# Main.net
KiCad netlist of a schematic drawn in Altium Designer
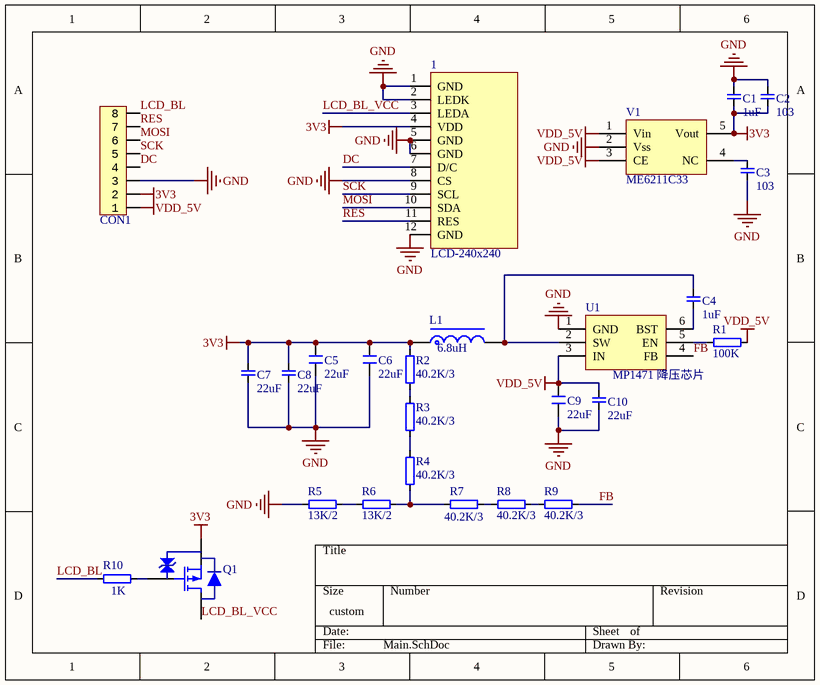
[diagram p0: Main.SchDoc]

(export (version "E")
  (design (tool "Eeschema 10.0.6"))
  (components
    (comp (ref "1")
      (value "LCD-240x240")
      (footprint "LCD-240x240-NoHole")
      (description "显示屏")
      (libsource (lib "ExtendBoard") (part "LCD-240x240"))
    )
    (comp (ref "C1") (value "1uF") (footprint "CAP_0603") (libsource (lib "基本元件库") (part "cap")))
    (comp (ref "C2") (value "103") (footprint "CAP_0603") (libsource (lib "基本元件库") (part "cap")))
    (comp (ref "C3") (value "103") (footprint "CAP_0603") (libsource (lib "基本元件库") (part "cap")))
    (comp (ref "C4") (value "1uF") (footprint "CAP_0603") (libsource (lib "基本元件库") (part "cap")))
    (comp (ref "C5")
      (value "22uF")
      (footprint "C 0805_L")
      (description "无极性贴片电容")
      (libsource (lib "ExtendBoard") (part "C"))
    )
    (comp (ref "C6")
      (value "22uF")
      (footprint "C 0805_L")
      (description "无极性贴片电容")
      (libsource (lib "ExtendBoard") (part "C"))
    )
    (comp (ref "C7") (value "22uF") (footprint "CAP_0603") (libsource (lib "基本元件库") (part "cap")))
    (comp (ref "C8") (value "22uF") (footprint "CAP_0603") (libsource (lib "基本元件库") (part "cap")))
    (comp (ref "C9")
      (value "22uF")
      (footprint "C 0805_L")
      (description "无极性贴片电容")
      (libsource (lib "ExtendBoard") (part "C"))
    )
    (comp (ref "C10") (value "22uF") (footprint "CAP_0603") (libsource (lib "基本元件库") (part "cap")))
    (comp (ref "CON1")
      (value "FFC_0.5_8")
      (footprint "FFC_0.5_8")
      (description "FFC")
      (libsource (lib "ExtendBoard") (part "FFC_0.5_8"))
    )
    (comp (ref "L1")
      (value "6.8uH")
      (footprint "NR4030")
      (description "NR磁胶电感")
      (libsource (lib "ExtendBoard") (part "L-NR"))
    )
    (comp (ref "Q1")
      (value "AO3415A")
      (footprint "SOT23-3")
      (description "MOSFET")
      (fields (field (name "PUBLISHER") "Altium Limited"))
      (libsource (lib "MyPcbLib") (part "AO3415A"))
    )
    (comp (ref "R1") (value "100K") (footprint "RES_0603") (libsource (lib "基本元件库") (part "Res")))
    (comp (ref "R2") (value "40.2K/3") (footprint "RES_0603") (libsource (lib "基本元件库") (part "Res")))
    (comp (ref "R3") (value "40.2K/3") (footprint "RES_0603") (libsource (lib "基本元件库") (part "Res")))
    (comp (ref "R4") (value "40.2K/3") (footprint "RES_0603") (libsource (lib "基本元件库") (part "Res")))
    (comp (ref "R5") (value "13K/2") (footprint "RES_0603") (libsource (lib "基本元件库") (part "Res")))
    (comp (ref "R6") (value "13K/2") (footprint "RES_0603") (libsource (lib "基本元件库") (part "Res")))
    (comp (ref "R7") (value "40.2K/3") (footprint "RES_0603") (libsource (lib "基本元件库") (part "Res")))
    (comp (ref "R8") (value "40.2K/3") (footprint "RES_0603") (libsource (lib "基本元件库") (part "Res")))
    (comp (ref "R9") (value "40.2K/3") (footprint "RES_0603") (libsource (lib "基本元件库") (part "Res")))
    (comp (ref "R10") (value "1K") (footprint "RES_0603") (libsource (lib "基本元件库") (part "Res")))
    (comp (ref "U1")
      (value "MP1471 降压芯片")
      (footprint "SOT23-6L")
      (description "DC降压芯片")
      (libsource (lib "ExtendBoard") (part "MP1471"))
    )
    (comp (ref "V1")
      (value "ME6211C33")
      (footprint "SOT23-5L")
      (description "低功耗LDO")
      (libsource (lib "ExtendBoard") (part "ME6211"))
    )
  )
  (nets
    (net (code "1") (name "/DC") (class "Default")
      (node (ref "1") (pin "7") (pinfunction "D/C_7") (pintype "passive"))
      (node (ref "CON1") (pin "4") (pinfunction "4_4") (pintype "passive"))
    )
    (net (code "2") (name "/FB") (class "Default")
      (node (ref "R9") (pin "1") (pinfunction "1_1") (pintype "passive"))
      (node (ref "U1") (pin "4") (pinfunction "FB_4") (pintype "passive"))
    )
    (net (code "3") (name "/LCD_BL") (class "Default")
      (node (ref "CON1") (pin "8") (pinfunction "8_8") (pintype "passive"))
      (node (ref "R10") (pin "2") (pinfunction "2_2") (pintype "passive"))
    )
    (net (code "4") (name "/LCD_BL_VCC") (class "Default")
      (node (ref "1") (pin "3") (pinfunction "LEDA_3") (pintype "passive"))
      (node (ref "Q1") (pin "3") (pinfunction "D_3") (pintype "passive"))
    )
    (net (code "5") (name "/MOSI") (class "Default")
      (node (ref "1") (pin "10") (pinfunction "SDA_10") (pintype "passive"))
      (node (ref "CON1") (pin "6") (pinfunction "6_6") (pintype "passive"))
    )
    (net (code "6") (name "/RES") (class "Default")
      (node (ref "1") (pin "11") (pinfunction "RES_11") (pintype "passive"))
      (node (ref "CON1") (pin "7") (pinfunction "7_7") (pintype "passive"))
    )
    (net (code "7") (name "/SCK") (class "Default")
      (node (ref "1") (pin "9") (pinfunction "SCL_9") (pintype "passive"))
      (node (ref "CON1") (pin "5") (pinfunction "5_5") (pintype "passive"))
    )
    (net (code "8") (name "3V3") (class "Default")
      (node (ref "1") (pin "4") (pinfunction "VDD_4") (pintype "passive"))
      (node (ref "C1") (pin "1") (pinfunction "1_1") (pintype "passive"))
      (node (ref "C2") (pin "1") (pinfunction "1_1") (pintype "passive"))
      (node (ref "C5") (pin "2") (pinfunction "2_2") (pintype "passive"))
      (node (ref "C6") (pin "2") (pinfunction "2_2") (pintype "passive"))
      (node (ref "C7") (pin "2") (pinfunction "2_2") (pintype "passive"))
      (node (ref "C8") (pin "2") (pinfunction "2_2") (pintype "passive"))
      (node (ref "CON1") (pin "2") (pinfunction "2_2") (pintype "passive"))
      (node (ref "L1") (pin "1") (pinfunction "1_1") (pintype "passive"))
      (node (ref "Q1") (pin "2") (pinfunction "S_2") (pintype "passive"))
      (node (ref "R2") (pin "2") (pinfunction "2_2") (pintype "passive"))
      (node (ref "V1") (pin "5") (pinfunction "Vout_5") (pintype "passive"))
    )
    (net (code "9") (name "GND") (class "Default")
      (node (ref "1") (pin "1") (pinfunction "GND_1") (pintype "passive"))
      (node (ref "1") (pin "12") (pinfunction "GND_12") (pintype "passive"))
      (node (ref "1") (pin "2") (pinfunction "LEDK_2") (pintype "passive"))
      (node (ref "1") (pin "5") (pinfunction "GND_5") (pintype "passive"))
      (node (ref "1") (pin "6") (pinfunction "GND_6") (pintype "passive"))
      (node (ref "1") (pin "8") (pinfunction "CS_8") (pintype "passive"))
      (node (ref "C1") (pin "2") (pinfunction "2_2") (pintype "passive"))
      (node (ref "C10") (pin "1") (pinfunction "1_1") (pintype "passive"))
      (node (ref "C2") (pin "2") (pinfunction "2_2") (pintype "passive"))
      (node (ref "C3") (pin "1") (pinfunction "1_1") (pintype "passive"))
      (node (ref "C5") (pin "1") (pinfunction "1_1") (pintype "passive"))
      (node (ref "C6") (pin "1") (pinfunction "1_1") (pintype "passive"))
      (node (ref "C7") (pin "1") (pinfunction "1_1") (pintype "passive"))
      (node (ref "C8") (pin "1") (pinfunction "1_1") (pintype "passive"))
      (node (ref "C9") (pin "1") (pinfunction "1_1") (pintype "passive"))
      (node (ref "CON1") (pin "3") (pinfunction "3_3") (pintype "passive"))
      (node (ref "R5") (pin "2") (pinfunction "2_2") (pintype "passive"))
      (node (ref "U1") (pin "1") (pinfunction "GND_1") (pintype "passive"))
      (node (ref "V1") (pin "2") (pinfunction "Vss_2") (pintype "passive"))
    )
    (net (code "10") (name "Net-(Q1-G)") (class "Default")
      (node (ref "Q1") (pin "1") (pinfunction "G_1") (pintype "passive"))
      (node (ref "R10") (pin "1") (pinfunction "1_1") (pintype "passive"))
    )
    (net (code "11") (name "Net-(R2-Pad1)") (class "Default")
      (node (ref "R2") (pin "1") (pinfunction "1_1") (pintype "passive"))
      (node (ref "R3") (pin "2") (pinfunction "2_2") (pintype "passive"))
    )
    (net (code "12") (name "Net-(R3-Pad1)") (class "Default")
      (node (ref "R3") (pin "1") (pinfunction "1_1") (pintype "passive"))
      (node (ref "R4") (pin "2") (pinfunction "2_2") (pintype "passive"))
    )
    (net (code "13") (name "Net-(R4-Pad1)") (class "Default")
      (node (ref "R4") (pin "1") (pinfunction "1_1") (pintype "passive"))
      (node (ref "R6") (pin "1") (pinfunction "1_1") (pintype "passive"))
      (node (ref "R7") (pin "2") (pinfunction "2_2") (pintype "passive"))
    )
    (net (code "14") (name "Net-(R5-Pad1)") (class "Default")
      (node (ref "R5") (pin "1") (pinfunction "1_1") (pintype "passive"))
      (node (ref "R6") (pin "2") (pinfunction "2_2") (pintype "passive"))
    )
    (net (code "15") (name "Net-(R7-Pad1)") (class "Default")
      (node (ref "R7") (pin "1") (pinfunction "1_1") (pintype "passive"))
      (node (ref "R8") (pin "2") (pinfunction "2_2") (pintype "passive"))
    )
    (net (code "16") (name "Net-(R8-Pad1)") (class "Default")
      (node (ref "R8") (pin "1") (pinfunction "1_1") (pintype "passive"))
      (node (ref "R9") (pin "2") (pinfunction "2_2") (pintype "passive"))
    )
    (net (code "17") (name "Net-(U1-BST)") (class "Default")
      (node (ref "C4") (pin "1") (pinfunction "1_1") (pintype "passive"))
      (node (ref "U1") (pin "6") (pinfunction "BST_6") (pintype "passive"))
    )
    (net (code "18") (name "Net-(U1-EN)") (class "Default")
      (node (ref "R1") (pin "2") (pinfunction "2_2") (pintype "passive"))
      (node (ref "U1") (pin "5") (pinfunction "EN_5") (pintype "passive"))
    )
    (net (code "19") (name "Net-(U1-SW)") (class "Default")
      (node (ref "C4") (pin "2") (pinfunction "2_2") (pintype "passive"))
      (node (ref "L1") (pin "2") (pinfunction "2_2") (pintype "passive"))
      (node (ref "U1") (pin "2") (pinfunction "SW_2") (pintype "passive"))
    )
    (net (code "20") (name "Net-(V1-NC)") (class "Default")
      (node (ref "C3") (pin "2") (pinfunction "2_2") (pintype "passive"))
      (node (ref "V1") (pin "4") (pinfunction "NC_4") (pintype "passive"))
    )
    (net (code "21") (name "VDD_5V") (class "Default")
      (node (ref "C10") (pin "2") (pinfunction "2_2") (pintype "passive"))
      (node (ref "C9") (pin "2") (pinfunction "2_2") (pintype "passive"))
      (node (ref "CON1") (pin "1") (pinfunction "1_1") (pintype "passive"))
      (node (ref "R1") (pin "1") (pinfunction "1_1") (pintype "passive"))
      (node (ref "U1") (pin "3") (pinfunction "IN_3") (pintype "passive"))
      (node (ref "V1") (pin "1") (pinfunction "Vin_1") (pintype "passive"))
      (node (ref "V1") (pin "3") (pinfunction "CE_3") (pintype "passive"))
    )
  )
)
